# BG0250TG_BW235_OV_9282.net
KiCad netlist of a schematic drawn in Altium Designer
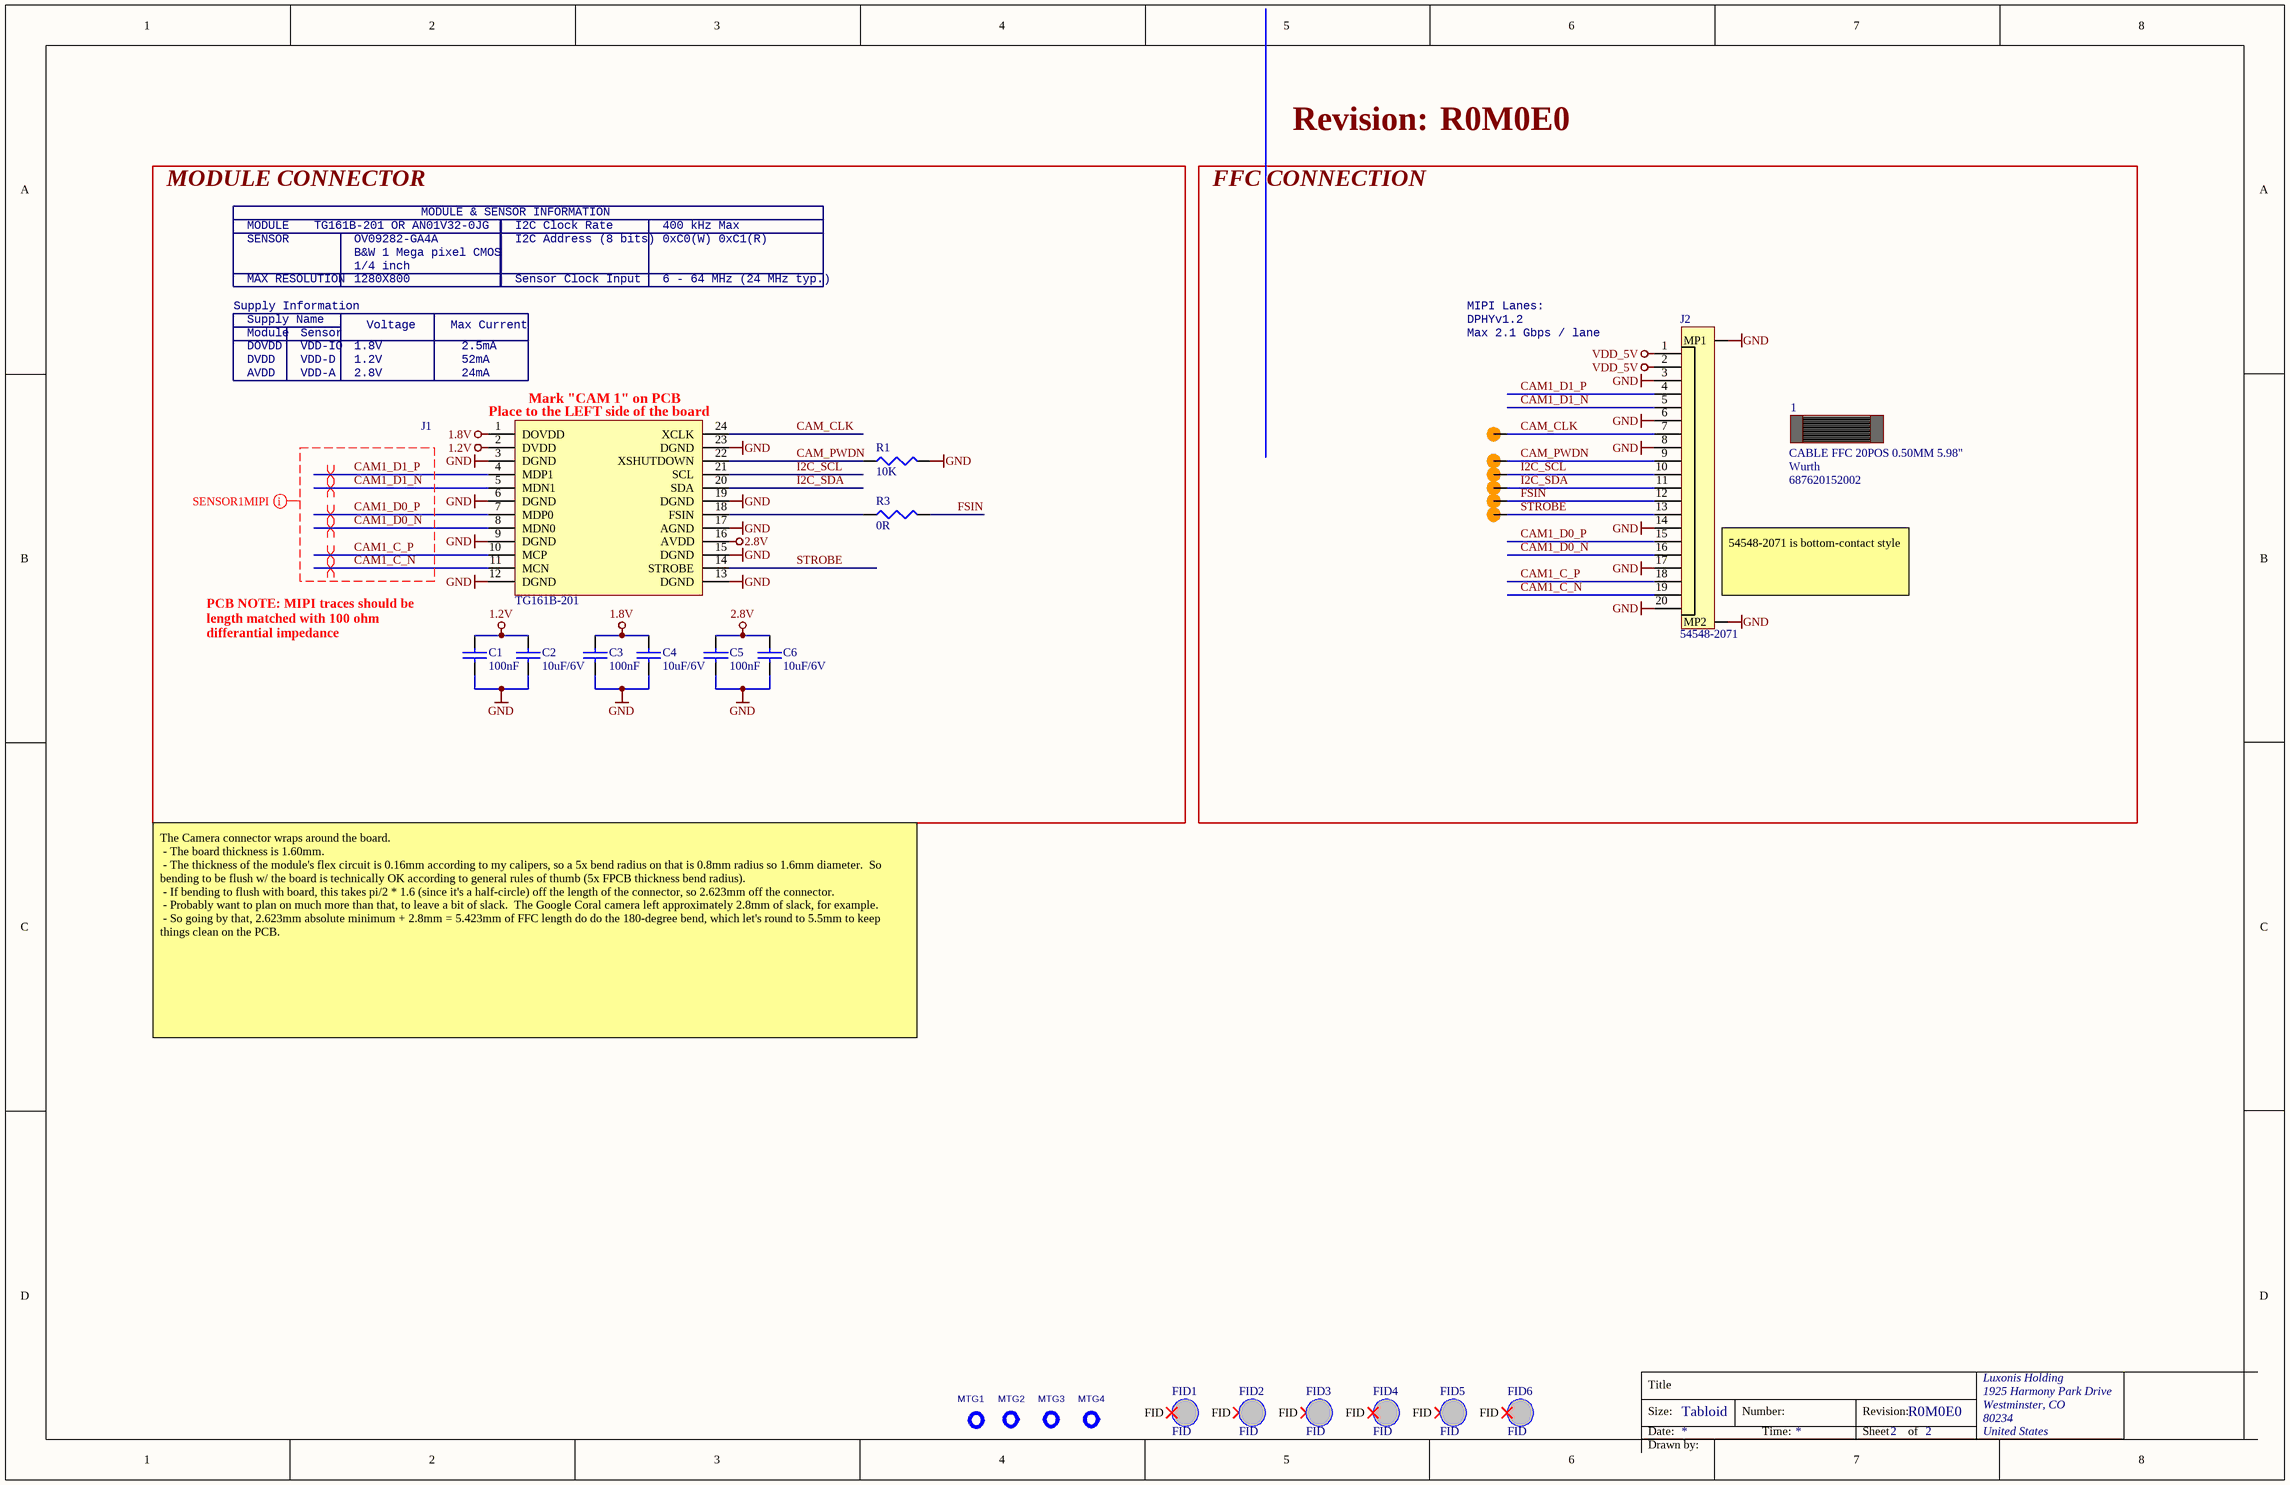
[diagram p0: BG0250TG_BW235_OV_9282.SchDoc]

(export (version "E")
  (design (tool "Eeschema 10.0.6"))
  (components
    (comp (ref "1")
      (value "687620152002")
      (description "20 pin FFC cable 15cm")
      (fields (field (name "ICCO PN") "CABLE FFC 20POS 0.50MM 5.98\"") (field (name "MAN") "Wurth"))
      (libsource (lib "RS-CONN") (part "26 pin FFC cable 15cm"))
    )
    (comp (ref "C1")
      (value "100nF")
      (footprint "0402")
      (description "SMD Multilayer Ceramic Capacitor, 0402 [1005 Metric], 0.1 µF, 10 V, ± 10%, X5R")
      (libsource (lib "MV0250_R0M0E0") (part "CAP"))
    )
    (comp (ref "C2")
      (value "10uF/6V")
      (footprint "0603")
      (description "CC0603MRX5R5BB106  SMD Multilayer Ceramic Capacitor, 0603 [1608 Metric], 10 µF, 6.3 V, ± 20%, X5R")
      (libsource (lib "MV0250_R0M0E0") (part "CAP"))
    )
    (comp (ref "C3")
      (value "100nF")
      (footprint "0402")
      (description "SMD Multilayer Ceramic Capacitor, 0402 [1005 Metric], 0.1 µF, 10 V, ± 10%, X5R")
      (libsource (lib "MV0250_R0M0E0") (part "CAP"))
    )
    (comp (ref "C4")
      (value "10uF/6V")
      (footprint "0603")
      (description "CC0603MRX5R5BB106  SMD Multilayer Ceramic Capacitor, 0603 [1608 Metric], 10 µF, 6.3 V, ± 20%, X5R")
      (libsource (lib "MV0250_R0M0E0") (part "CAP"))
    )
    (comp (ref "C5")
      (value "100nF")
      (footprint "0402")
      (description "SMD Multilayer Ceramic Capacitor, 0402 [1005 Metric], 0.1 µF, 10 V, ± 10%, X5R")
      (libsource (lib "MV0250_R0M0E0") (part "CAP"))
    )
    (comp (ref "C6")
      (value "10uF/6V")
      (footprint "0603")
      (description "CC0603MRX5R5BB106  SMD Multilayer Ceramic Capacitor, 0603 [1608 Metric], 10 µF, 6.3 V, ± 20%, X5R")
      (libsource (lib "MV0250_R0M0E0") (part "CAP"))
    )
    (comp (ref "FID1")
      (value "FID")
      (footprint "Luxonis:FIDUCIAL_1MM")
      (description "Fiducial mark")
      (libsource (lib "MV0250_R0M0E0") (part "FID"))
    )
    (comp (ref "FID2")
      (value "FID")
      (footprint "Luxonis:FIDUCIAL_1MM")
      (description "Fiducial mark")
      (libsource (lib "MV0250_R0M0E0") (part "FID"))
    )
    (comp (ref "FID3")
      (value "FID")
      (footprint "Luxonis:FIDUCIAL_1MM")
      (description "Fiducial mark")
      (libsource (lib "MV0250_R0M0E0") (part "FID"))
    )
    (comp (ref "FID4")
      (value "FID")
      (footprint "Luxonis:FIDUCIAL_1MM")
      (description "Fiducial mark")
      (libsource (lib "MV0250_R0M0E0") (part "FID"))
    )
    (comp (ref "FID5")
      (value "FID")
      (footprint "Luxonis:FIDUCIAL_1MM")
      (description "Fiducial mark")
      (libsource (lib "MV0250_R0M0E0") (part "FID"))
    )
    (comp (ref "FID6")
      (value "FID")
      (footprint "Luxonis:FIDUCIAL_1MM")
      (description "Fiducial mark")
      (libsource (lib "MV0250_R0M0E0") (part "FID"))
    )
    (comp (ref "J1")
      (value "TG161B-201")
      (footprint "BG0250TG:TG161B-201 / AN01V32 - Board Wrap")
      (description "24 way, 2row baord to board connector SMD")
      (libsource (lib "MV0250_R0M0E0") (part "TG161B-201"))
    )
    (comp (ref "J2")
      (value "54548-2071")
      (footprint "Luxonis:545482071")
      (description "FFC & FPC Connectors 0.5 FPC ZIF Hsg Assy ssy 20Ckt EmbsTp Pkg")
      (fields
        (field (name "MANUFACTURER_PART_NUMBER") "54548-2271")
        (field (name "MOUSER PART NUMBER") "538-54548-2271")
      )
      (libsource (lib "Luxonis") (part "54548-2071"))
    )
    (comp (ref "MTG1")
      (value "MTG-HOLE")
      (footprint "Luxonis:Hole_2.2mm")
      (description "Mounting Hole")
      (libsource (lib "Luxonis") (part "MTG-HOLE-NO-PLATE"))
    )
    (comp (ref "MTG2")
      (value "MTG-HOLE")
      (footprint "Luxonis:Hole_2.2mm")
      (description "Mounting Hole")
      (libsource (lib "Luxonis") (part "MTG-HOLE-NO-PLATE"))
    )
    (comp (ref "MTG3")
      (value "MTG-HOLE")
      (footprint "Luxonis:Hole_2.2mm")
      (description "Mounting Hole")
      (libsource (lib "Luxonis") (part "MTG-HOLE-NO-PLATE"))
    )
    (comp (ref "MTG4")
      (value "MTG-HOLE")
      (footprint "Luxonis:Hole_2.2mm")
      (description "Mounting Hole")
      (libsource (lib "Luxonis") (part "MTG-HOLE-NO-PLATE"))
    )
    (comp (ref "R1")
      (value "10K")
      (footprint "0603")
      (description "SMD Chip Resistor, 10 kohm, 75 V, 0603 [1608 Metric], 100 mW, ± 1%")
      (libsource (lib "MV0250_R0M0E0") (part "RES1"))
    )
    (comp (ref "R3")
      (value "0R")
      (footprint "0603")
      (description "SMD Chip Resistor, Thick Film, 0 ohm, 75 V, 0603 [1608 Metric], 100 mW")
      (libsource (lib "MV0250_R0M0E0") (part "RES1"))
    )
    (comp (ref "TP1")
      (value "TP_SMD")
      (footprint "TP_0.75MM_SMD_NO-SILK")
      (description "circular pad test point, SMD")
      (libsource (lib "Luxonis") (part "TP_SMD"))
    )
    (comp (ref "TP2")
      (value "TP_SMD")
      (footprint "TP_0.75MM_SMD_NO-SILK")
      (description "circular pad test point, SMD")
      (libsource (lib "Luxonis") (part "TP_SMD"))
    )
    (comp (ref "TP3")
      (value "TP_SMD")
      (footprint "TP_0.75MM_SMD_NO-SILK")
      (description "circular pad test point, SMD")
      (libsource (lib "Luxonis") (part "TP_SMD"))
    )
    (comp (ref "TP4")
      (value "TP_SMD")
      (footprint "TP_0.75MM_SMD_NO-SILK")
      (description "circular pad test point, SMD")
      (libsource (lib "Luxonis") (part "TP_SMD"))
    )
    (comp (ref "TP5")
      (value "TP_SMD")
      (footprint "TP_0.75MM_SMD_NO-SILK")
      (description "circular pad test point, SMD")
      (libsource (lib "Luxonis") (part "TP_SMD"))
    )
    (comp (ref "TP6")
      (value "TP_SMD")
      (footprint "TP_0.75MM_SMD_NO-SILK")
      (description "circular pad test point, SMD")
      (libsource (lib "Luxonis") (part "TP_SMD"))
    )
  )
  (nets
    (net (code "1") (name "/CAM1_C_N") (class "Default")
      (node (ref "J1") (pin "11") (pinfunction "MCN_11") (pintype "passive"))
      (node (ref "J2") (pin "19") (pinfunction "19_19") (pintype "passive"))
    )
    (net (code "2") (name "/CAM1_C_P") (class "Default")
      (node (ref "J1") (pin "10") (pinfunction "MCP_10") (pintype "passive"))
      (node (ref "J2") (pin "18") (pinfunction "18_18") (pintype "passive"))
    )
    (net (code "3") (name "/CAM1_D0_N") (class "Default")
      (node (ref "J1") (pin "8") (pinfunction "MDN0_8") (pintype "passive"))
      (node (ref "J2") (pin "16") (pinfunction "16_16") (pintype "passive"))
    )
    (net (code "4") (name "/CAM1_D0_P") (class "Default")
      (node (ref "J1") (pin "7") (pinfunction "MDP0_7") (pintype "passive"))
      (node (ref "J2") (pin "15") (pinfunction "15_15") (pintype "passive"))
    )
    (net (code "5") (name "/CAM1_D1_N") (class "Default")
      (node (ref "J1") (pin "5") (pinfunction "MDN1_5") (pintype "passive"))
      (node (ref "J2") (pin "5") (pinfunction "5_5") (pintype "passive"))
    )
    (net (code "6") (name "/CAM1_D1_P") (class "Default")
      (node (ref "J1") (pin "4") (pinfunction "MDP1_4") (pintype "passive"))
      (node (ref "J2") (pin "4") (pinfunction "4_4") (pintype "passive"))
    )
    (net (code "7") (name "/CAM_CLK") (class "Default")
      (node (ref "J1") (pin "24") (pinfunction "XCLK_24") (pintype "passive"))
      (node (ref "J2") (pin "7") (pinfunction "7_7") (pintype "passive"))
      (node (ref "TP1") (pin "1") (pintype "passive"))
    )
    (net (code "8") (name "/CAM_PWDN") (class "Default")
      (node (ref "J1") (pin "22") (pinfunction "XSHUTDOWN_22") (pintype "passive"))
      (node (ref "J2") (pin "9") (pinfunction "9_9") (pintype "passive"))
      (node (ref "R1") (pin "1") (pintype "passive"))
      (node (ref "TP2") (pin "1") (pintype "passive"))
    )
    (net (code "9") (name "/FSIN") (class "Default")
      (node (ref "J2") (pin "12") (pinfunction "12_12") (pintype "passive"))
      (node (ref "R3") (pin "2") (pintype "passive"))
      (node (ref "TP5") (pin "1") (pintype "passive"))
    )
    (net (code "10") (name "/I2C_SCL") (class "Default")
      (node (ref "J1") (pin "21") (pinfunction "SCL_21") (pintype "passive"))
      (node (ref "J2") (pin "10") (pinfunction "10_10") (pintype "passive"))
      (node (ref "TP3") (pin "1") (pintype "passive"))
    )
    (net (code "11") (name "/I2C_SDA") (class "Default")
      (node (ref "J1") (pin "20") (pinfunction "SDA_20") (pintype "passive"))
      (node (ref "J2") (pin "11") (pinfunction "11_11") (pintype "passive"))
      (node (ref "TP4") (pin "1") (pintype "passive"))
    )
    (net (code "12") (name "/STROBE") (class "Default")
      (node (ref "J1") (pin "14") (pinfunction "STROBE_14") (pintype "passive"))
      (node (ref "J2") (pin "13") (pinfunction "13_13") (pintype "passive"))
      (node (ref "TP6") (pin "1") (pintype "passive"))
    )
    (net (code "13") (name "1.2V") (class "Default")
      (node (ref "C1") (pin "2") (pinfunction "2_2") (pintype "passive"))
      (node (ref "C2") (pin "2") (pinfunction "2_2") (pintype "passive"))
      (node (ref "J1") (pin "2") (pinfunction "DVDD_2") (pintype "passive"))
    )
    (net (code "14") (name "1.8V") (class "Default")
      (node (ref "C3") (pin "2") (pinfunction "2_2") (pintype "passive"))
      (node (ref "C4") (pin "2") (pinfunction "2_2") (pintype "passive"))
      (node (ref "J1") (pin "1") (pinfunction "DOVDD_1") (pintype "passive"))
    )
    (net (code "15") (name "2.8V") (class "Default")
      (node (ref "C5") (pin "2") (pinfunction "2_2") (pintype "passive"))
      (node (ref "C6") (pin "2") (pinfunction "2_2") (pintype "passive"))
      (node (ref "J1") (pin "16") (pinfunction "AVDD_16") (pintype "passive"))
    )
    (net (code "16") (name "GND") (class "Default")
      (node (ref "C1") (pin "1") (pinfunction "1_1") (pintype "passive"))
      (node (ref "C2") (pin "1") (pinfunction "1_1") (pintype "passive"))
      (node (ref "C3") (pin "1") (pinfunction "1_1") (pintype "passive"))
      (node (ref "C4") (pin "1") (pinfunction "1_1") (pintype "passive"))
      (node (ref "C5") (pin "1") (pinfunction "1_1") (pintype "passive"))
      (node (ref "C6") (pin "1") (pinfunction "1_1") (pintype "passive"))
      (node (ref "J1") (pin "12") (pinfunction "DGND_12") (pintype "passive"))
      (node (ref "J1") (pin "13") (pinfunction "DGND_13") (pintype "passive"))
      (node (ref "J1") (pin "15") (pinfunction "DGND_15") (pintype "passive"))
      (node (ref "J1") (pin "17") (pinfunction "AGND_17") (pintype "passive"))
      (node (ref "J1") (pin "19") (pinfunction "DGND_19") (pintype "passive"))
      (node (ref "J1") (pin "23") (pinfunction "DGND_23") (pintype "passive"))
      (node (ref "J1") (pin "3") (pinfunction "DGND_3") (pintype "passive"))
      (node (ref "J1") (pin "6") (pinfunction "DGND_6") (pintype "passive"))
      (node (ref "J1") (pin "9") (pinfunction "DGND_9") (pintype "passive"))
      (node (ref "J2") (pin "14") (pinfunction "14_14") (pintype "passive"))
      (node (ref "J2") (pin "17") (pinfunction "17_17") (pintype "passive"))
      (node (ref "J2") (pin "20") (pinfunction "20_20") (pintype "passive"))
      (node (ref "J2") (pin "3") (pinfunction "3_3") (pintype "passive"))
      (node (ref "J2") (pin "6") (pinfunction "6_6") (pintype "passive"))
      (node (ref "J2") (pin "8") (pinfunction "8_8") (pintype "passive"))
      (node (ref "J2") (pin "MP1") (pinfunction "MP1_MP1") (pintype "passive"))
      (node (ref "J2") (pin "MP2") (pinfunction "MP2_MP2") (pintype "passive"))
      (node (ref "R1") (pin "2") (pintype "passive"))
    )
    (net (code "17") (name "Net-(J1-FSIN)") (class "Default")
      (node (ref "J1") (pin "18") (pinfunction "FSIN_18") (pintype "passive"))
      (node (ref "R3") (pin "1") (pintype "passive"))
    )
    (net (code "18") (name "VDD_5V") (class "Default")
      (node (ref "J2") (pin "1") (pinfunction "1_1") (pintype "passive"))
      (node (ref "J2") (pin "2") (pinfunction "2_2") (pintype "passive"))
    )
    (net (code "19") (name "unconnected-(FID1-PadFID)") (class "Default")
      (node (ref "FID1") (pin "FID") (pinfunction "FID_FID") (pintype "input+no_connect"))
    )
    (net (code "20") (name "unconnected-(FID2-PadFID)") (class "Default")
      (node (ref "FID2") (pin "FID") (pinfunction "FID_FID") (pintype "input+no_connect"))
    )
    (net (code "21") (name "unconnected-(FID3-PadFID)") (class "Default")
      (node (ref "FID3") (pin "FID") (pinfunction "FID_FID") (pintype "input+no_connect"))
    )
    (net (code "22") (name "unconnected-(FID4-PadFID)") (class "Default")
      (node (ref "FID4") (pin "FID") (pinfunction "FID_FID") (pintype "input+no_connect"))
    )
    (net (code "23") (name "unconnected-(FID5-PadFID)") (class "Default")
      (node (ref "FID5") (pin "FID") (pinfunction "FID_FID") (pintype "input+no_connect"))
    )
    (net (code "24") (name "unconnected-(FID6-PadFID)") (class "Default")
      (node (ref "FID6") (pin "FID") (pinfunction "FID_FID") (pintype "input+no_connect"))
    )
  )
)
